# mcu-com-gpio-tim.net
KiCad netlist of a schematic drawn in Altium Designer
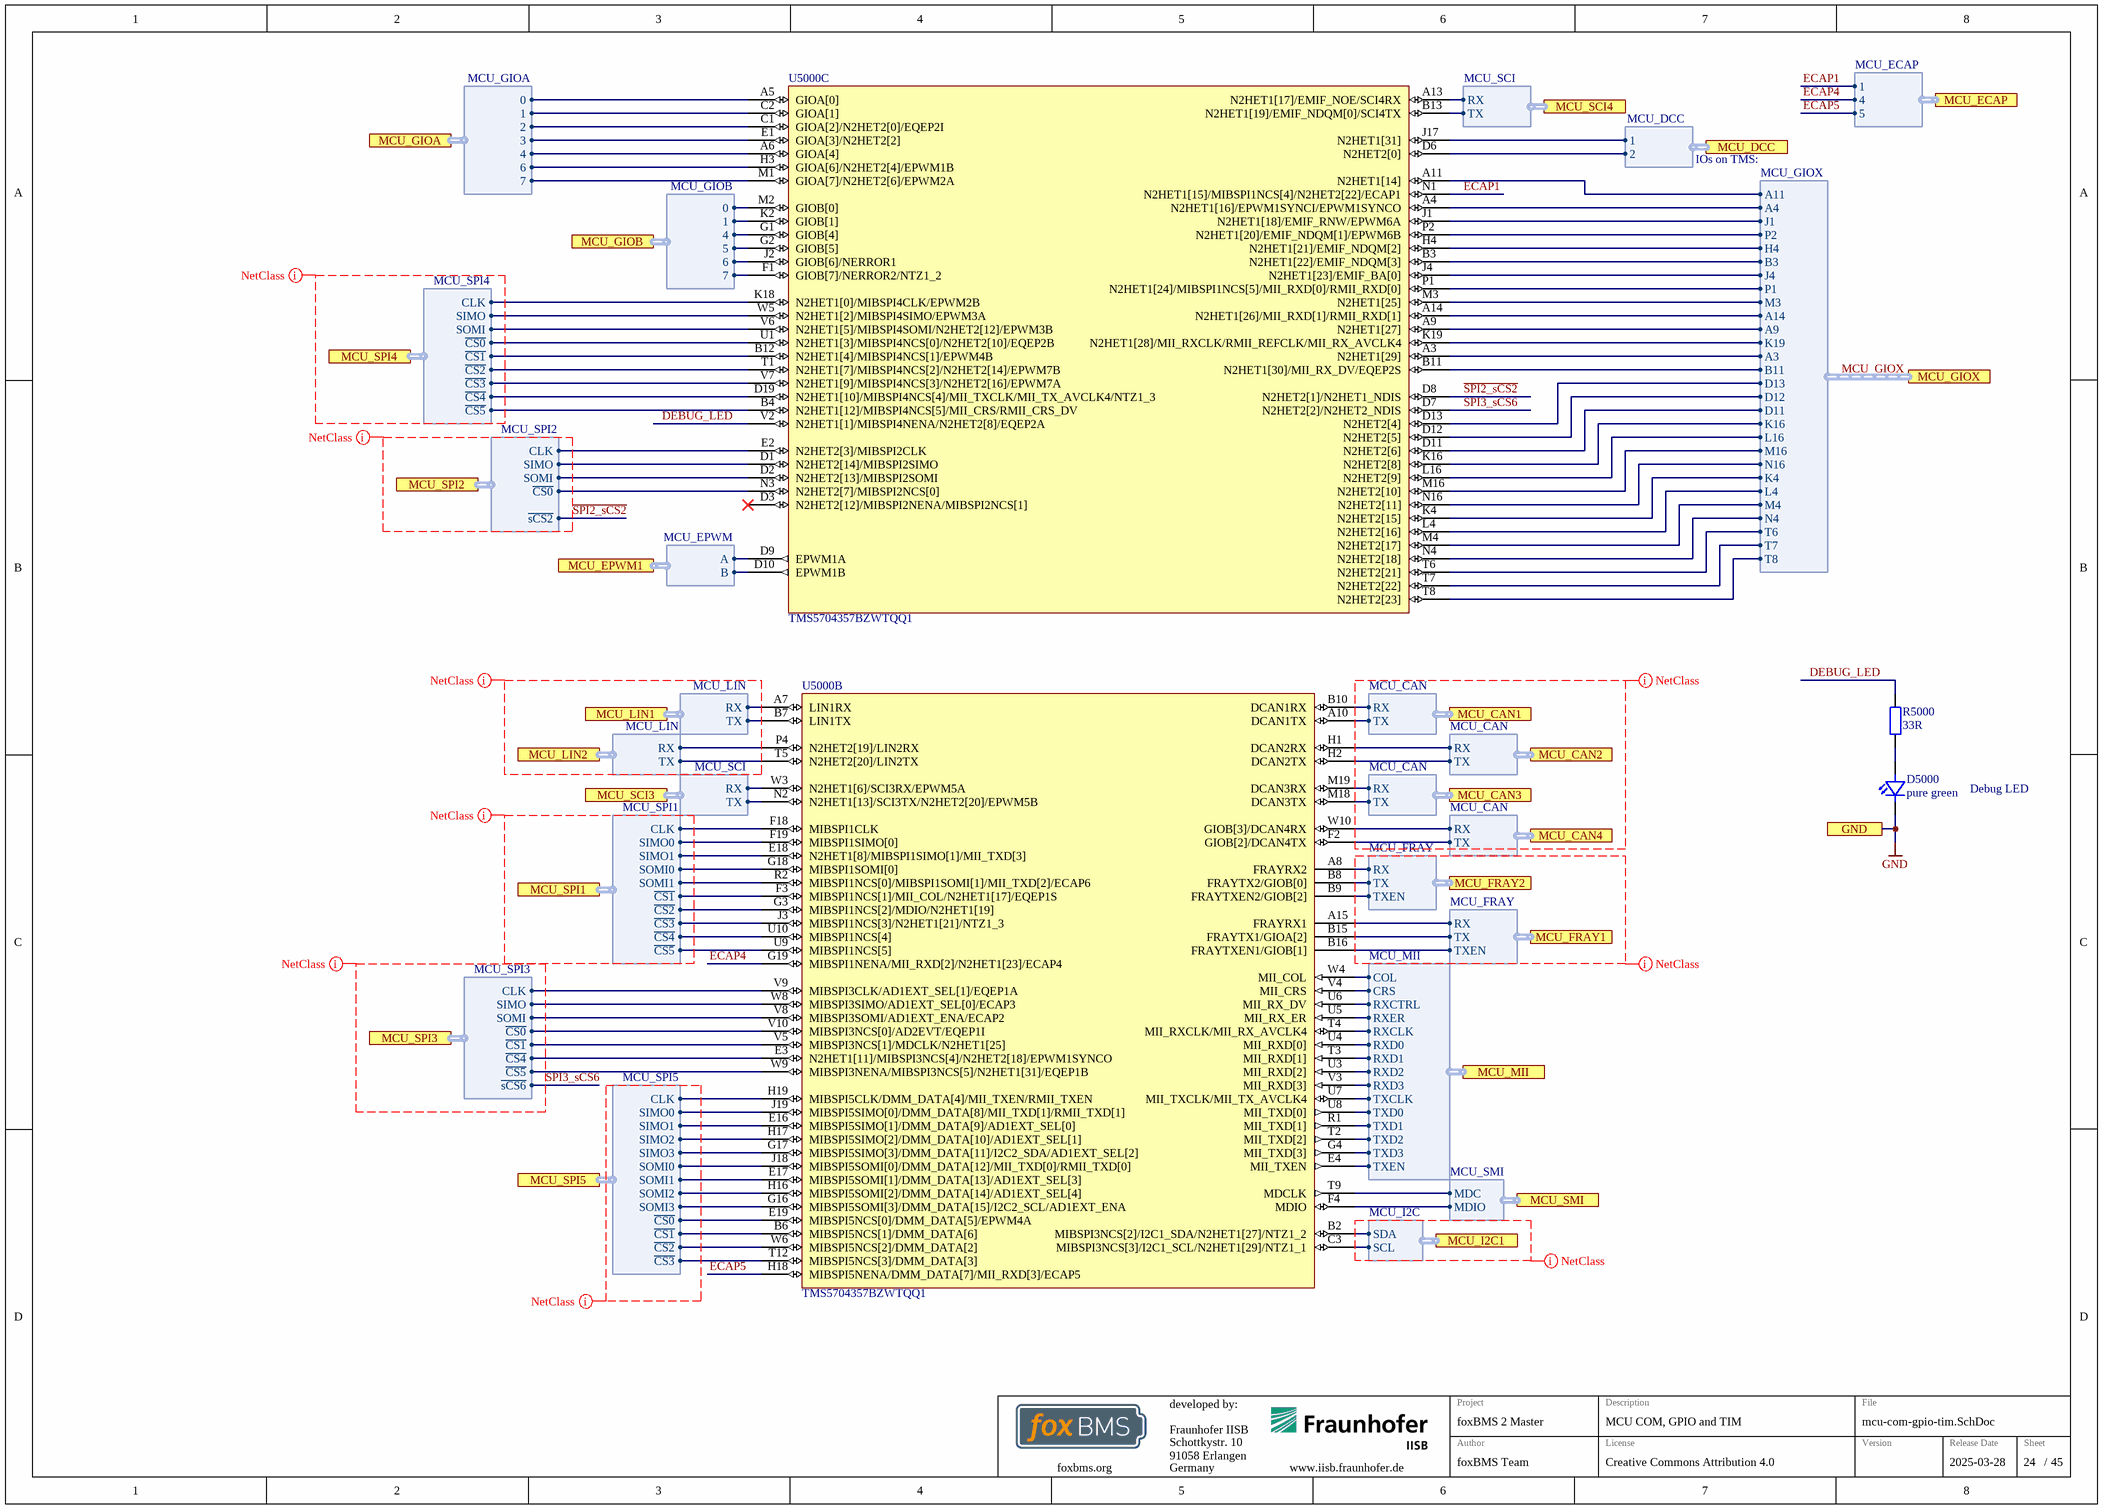
[diagram p0: mcu-com-gpio-tim.SchDoc]

(export (version "E")
  (design (tool "Eeschema 10.0.6"))
  (components
    (comp (ref "D5000")
      (value "pure green")
      (footprint "LEDC1608X07N")
      (description "TLMP1100-GS08")
      (fields (field (name "PART NUMBER") "LED_0603_pure_green_AECQ") (field (name "MANUFACTURER") "Vishay"))
      (libsource (lib "OE750") (part "D_LED"))
    )
    (comp (ref "R5000")
      (value "33R")
      (footprint "RESC1005X04N")
      (description "SMD Resistor 33R 0402")
      (fields (field (name "PART NUMBER") "gen_R_33R_0402") (field (name "TOLERANCE") "1%"))
      (libsource (lib "OE750") (part "R"))
    )
    (comp (ref "U5000")
      (value "TMS5704357BZWTQQ1")
      (footprint "BGA337C80P19X19_1600X1600X140")
      (libsource (lib "TMS570LC4357") (part "TMS5704357BZWTQQ1"))
    )
  )
  (nets
    (net (code "19") (name "/3") (class "Default")
      (node (ref "U5000") (pin "E1") (pinfunction "GIOA[3]/N2HET2[2]_E1") (pintype "bidirectional"))
    )
    (net (code "20") (name "/A") (class "Default")
      (node (ref "U5000") (pin "D9") (pinfunction "EPWM1A_D9") (pintype "output"))
    )
    (net (code "21") (name "/A3") (class "Default")
      (node (ref "U5000") (pin "A3") (pinfunction "N2HET1[29]_A3") (pintype "bidirectional"))
    )
    (net (code "22") (name "/A4") (class "Default")
      (node (ref "U5000") (pin "A4") (pinfunction "N2HET1[16]/EPWM1SYNCI/EPWM1SYNCO_A4") (pintype "bidirectional"))
    )
    (net (code "23") (name "/A9") (class "Default")
      (node (ref "U5000") (pin "A9") (pinfunction "N2HET1[27]_A9") (pintype "bidirectional"))
    )
    (net (code "24") (name "/A11") (class "Default")
      (node (ref "U5000") (pin "A11") (pinfunction "N2HET1[14]_A11") (pintype "bidirectional"))
    )
    (net (code "25") (name "/A14") (class "Default")
      (node (ref "U5000") (pin "A14") (pinfunction "N2HET1[26]/MII_RXD[1]/RMII_RXD[1]_A14") (pintype "bidirectional"))
    )
    (net (code "26") (name "/B") (class "Default")
      (node (ref "U5000") (pin "D10") (pinfunction "EPWM1B_D10") (pintype "output"))
    )
    (net (code "27") (name "/B3") (class "Default")
      (node (ref "U5000") (pin "B3") (pinfunction "N2HET1[22]/EMIF_NDQM[3]_B3") (pintype "bidirectional"))
    )
    (net (code "28") (name "/B11") (class "Default")
      (node (ref "U5000") (pin "B11") (pinfunction "N2HET1[30]/MII_RX_DV/EQEP2S_B11") (pintype "bidirectional"))
    )
    (net (code "29") (name "/COL") (class "Default")
      (node (ref "U5000") (pin "W4") (pinfunction "MII_COL_W4") (pintype "input"))
    )
    (net (code "30") (name "/CRS") (class "Default")
      (node (ref "U5000") (pin "V4") (pinfunction "MII_CRS_V4") (pintype "input"))
    )
    (net (code "31") (name "/D11") (class "Default")
      (node (ref "U5000") (pin "D11") (pinfunction "N2HET2[6]_D11") (pintype "bidirectional"))
    )
    (net (code "32") (name "/D12") (class "Default")
      (node (ref "U5000") (pin "D12") (pinfunction "N2HET2[5]_D12") (pintype "bidirectional"))
    )
    (net (code "33") (name "/D13") (class "Default")
      (node (ref "U5000") (pin "D13") (pinfunction "N2HET2[4]_D13") (pintype "bidirectional"))
    )
    (net (code "34") (name "/DEBUG_LED") (class "Default")
      (node (ref "R5000") (pin "2") (pinfunction "2_2") (pintype "passive"))
      (node (ref "U5000") (pin "V2") (pinfunction "N2HET1[1]/MIBSPI4NENA/N2HET2[8]/EQEP2A_V2") (pintype "bidirectional"))
    )
    (net (code "35") (name "/ECAP1") (class "Default")
      (node (ref "U5000") (pin "N1") (pinfunction "N2HET1[15]/MIBSPI1NCS[4]/N2HET2[22]/ECAP1_N1") (pintype "bidirectional"))
    )
    (net (code "36") (name "/ECAP4") (class "Default")
      (node (ref "U5000") (pin "G19") (pinfunction "MIBSPI1NENA/MII_RXD[2]/N2HET1[23]/ECAP4_G19") (pintype "bidirectional"))
    )
    (net (code "37") (name "/ECAP5") (class "Default")
      (node (ref "U5000") (pin "H18") (pinfunction "MIBSPI5NENA/DMM_DATA[7]/MII_RXD[3]/ECAP5_H18") (pintype "bidirectional"))
    )
    (net (code "38") (name "/H4") (class "Default")
      (node (ref "U5000") (pin "H4") (pinfunction "N2HET1[21]/EMIF_NDQM[2]_H4") (pintype "bidirectional"))
    )
    (net (code "39") (name "/J1") (class "Default")
      (node (ref "U5000") (pin "J1") (pinfunction "N2HET1[18]/EMIF_RNW/EPWM6A_J1") (pintype "bidirectional"))
    )
    (net (code "40") (name "/J4") (class "Default")
      (node (ref "U5000") (pin "J4") (pinfunction "N2HET1[23]/EMIF_BA[0]_J4") (pintype "bidirectional"))
    )
    (net (code "41") (name "/K4") (class "Default")
      (node (ref "U5000") (pin "K4") (pinfunction "N2HET2[15]_K4") (pintype "bidirectional"))
    )
    (net (code "42") (name "/K16") (class "Default")
      (node (ref "U5000") (pin "K16") (pinfunction "N2HET2[8]_K16") (pintype "bidirectional"))
    )
    (net (code "43") (name "/K19") (class "Default")
      (node (ref "U5000") (pin "K19") (pinfunction "N2HET1[28]/MII_RXCLK/RMII_REFCLK/MII_RX_AVCLK4_K19") (pintype "bidirectional"))
    )
    (net (code "44") (name "/L4") (class "Default")
      (node (ref "U5000") (pin "L4") (pinfunction "N2HET2[16]_L4") (pintype "bidirectional"))
    )
    (net (code "45") (name "/L16") (class "Default")
      (node (ref "U5000") (pin "L16") (pinfunction "N2HET2[9]_L16") (pintype "bidirectional"))
    )
    (net (code "46") (name "/M3") (class "Default")
      (node (ref "U5000") (pin "M3") (pinfunction "N2HET1[25]_M3") (pintype "bidirectional"))
    )
    (net (code "47") (name "/M4") (class "Default")
      (node (ref "U5000") (pin "M4") (pinfunction "N2HET2[17]_M4") (pintype "bidirectional"))
    )
    (net (code "48") (name "/M16") (class "Default")
      (node (ref "U5000") (pin "M16") (pinfunction "N2HET2[10]_M16") (pintype "bidirectional"))
    )
    (net (code "50") (name "/MDC") (class "Default")
      (node (ref "U5000") (pin "T9") (pinfunction "MDCLK_T9") (pintype "output"))
    )
    (net (code "51") (name "/MDIO") (class "Default")
      (node (ref "U5000") (pin "F4") (pinfunction "MDIO_F4") (pintype "bidirectional"))
    )
    (net (code "52") (name "/N4") (class "Default")
      (node (ref "U5000") (pin "N4") (pinfunction "N2HET2[18]_N4") (pintype "bidirectional"))
    )
    (net (code "53") (name "/N16") (class "Default")
      (node (ref "U5000") (pin "N16") (pinfunction "N2HET2[11]_N16") (pintype "bidirectional"))
    )
    (net (code "54") (name "/P1") (class "Default")
      (node (ref "U5000") (pin "P1") (pinfunction "N2HET1[24]/MIBSPI1NCS[5]/MII_RXD[0]/RMII_RXD[0]_P1") (pintype "bidirectional"))
    )
    (net (code "55") (name "/P2") (class "Default")
      (node (ref "U5000") (pin "P2") (pinfunction "N2HET1[20]/EMIF_NDQM[1]/EPWM6B_P2") (pintype "bidirectional"))
    )
    (net (code "56") (name "/RXCLK") (class "Default")
      (node (ref "U5000") (pin "T4") (pinfunction "MII_RXCLK/MII_RX_AVCLK4_T4") (pintype "bidirectional"))
    )
    (net (code "57") (name "/RXCTRL") (class "Default")
      (node (ref "U5000") (pin "U6") (pinfunction "MII_RX_DV_U6") (pintype "input"))
    )
    (net (code "58") (name "/RXD0") (class "Default")
      (node (ref "U5000") (pin "U4") (pinfunction "MII_RXD[0]_U4") (pintype "input"))
    )
    (net (code "59") (name "/RXD1") (class "Default")
      (node (ref "U5000") (pin "T3") (pinfunction "MII_RXD[1]_T3") (pintype "input"))
    )
    (net (code "60") (name "/RXD2") (class "Default")
      (node (ref "U5000") (pin "U3") (pinfunction "MII_RXD[2]_U3") (pintype "input"))
    )
    (net (code "61") (name "/RXD3") (class "Default")
      (node (ref "U5000") (pin "V3") (pinfunction "MII_RXD[3]_V3") (pintype "input"))
    )
    (net (code "62") (name "/RXER") (class "Default")
      (node (ref "U5000") (pin "U5") (pinfunction "MII_RX_ER_U5") (pintype "input"))
    )
    (net (code "63") (name "/SCL") (class "Default")
      (node (ref "U5000") (pin "C3") (pinfunction "MIBSPI3NCS[3]/I2C1_SCL/N2HET1[29]/NTZ1_1_C3") (pintype "bidirectional"))
    )
    (net (code "64") (name "/SDA") (class "Default")
      (node (ref "U5000") (pin "B2") (pinfunction "MIBSPI3NCS[2]/I2C1_SDA/N2HET1[27]/NTZ1_2_B2") (pintype "bidirectional"))
    )
    (net (code "65") (name "/SIMO2") (class "Default")
      (node (ref "U5000") (pin "H17") (pinfunction "MIBSPI5SIMO[2]/DMM_DATA[10]/AD1EXT_SEL[1]_H17") (pintype "bidirectional"))
    )
    (net (code "66") (name "/SIMO3") (class "Default")
      (node (ref "U5000") (pin "G17") (pinfunction "MIBSPI5SIMO[3]/DMM_DATA[11]/I2C2_SDA/AD1EXT_SEL[2]_G17") (pintype "bidirectional"))
    )
    (net (code "67") (name "/SOMI2") (class "Default")
      (node (ref "U5000") (pin "H16") (pinfunction "MIBSPI5SOMI[2]/DMM_DATA[14]/AD1EXT_SEL[4]_H16") (pintype "bidirectional"))
    )
    (net (code "68") (name "/SOMI3") (class "Default")
      (node (ref "U5000") (pin "G16") (pinfunction "MIBSPI5SOMI[3]/DMM_DATA[15]/I2C2_SCL/AD1EXT_ENA_G16") (pintype "bidirectional"))
    )
    (net (code "69") (name "/SPI2_sCS2") (class "Default")
      (node (ref "U5000") (pin "D8") (pinfunction "N2HET2[1]/N2HET1_NDIS_D8") (pintype "bidirectional"))
    )
    (net (code "70") (name "/SPI3_sCS6") (class "Default")
      (node (ref "U5000") (pin "D7") (pinfunction "N2HET2[2]/N2HET2_NDIS_D7") (pintype "bidirectional"))
    )
    (net (code "71") (name "/T6") (class "Default")
      (node (ref "U5000") (pin "T6") (pinfunction "N2HET2[21]_T6") (pintype "bidirectional"))
    )
    (net (code "72") (name "/T7") (class "Default")
      (node (ref "U5000") (pin "T7") (pinfunction "N2HET2[22]_T7") (pintype "bidirectional"))
    )
    (net (code "73") (name "/T8") (class "Default")
      (node (ref "U5000") (pin "T8") (pinfunction "N2HET2[23]_T8") (pintype "bidirectional"))
    )
    (net (code "74") (name "/TXCLK") (class "Default")
      (node (ref "U5000") (pin "U7") (pinfunction "MII_TXCLK/MII_TX_AVCLK4_U7") (pintype "bidirectional"))
    )
    (net (code "75") (name "/TXD0") (class "Default")
      (node (ref "U5000") (pin "U8") (pinfunction "MII_TXD[0]_U8") (pintype "output"))
    )
    (net (code "76") (name "/TXD1") (class "Default")
      (node (ref "U5000") (pin "R1") (pinfunction "MII_TXD[1]_R1") (pintype "output"))
    )
    (net (code "77") (name "/TXD2") (class "Default")
      (node (ref "U5000") (pin "T2") (pinfunction "MII_TXD[2]_T2") (pintype "output"))
    )
    (net (code "78") (name "/TXD3") (class "Default")
      (node (ref "U5000") (pin "G4") (pinfunction "MII_TXD[3]_G4") (pintype "output"))
    )
    (net (code "96") (name "GND") (class "Default")
      (node (ref "D5000") (pin "1") (pinfunction "C_1") (pintype "passive"))
    )
    (net (code "97") (name "Net-(D5000-A)") (class "Default")
      (node (ref "D5000") (pin "2") (pinfunction "A_2") (pintype "passive"))
      (node (ref "R5000") (pin "1") (pinfunction "1_1") (pintype "passive"))
    )
    (net (code "98") (name "unconnected-(U5000B-DCAN1RX-PadB10)") (class "Default")
      (node (ref "U5000") (pin "B10") (pinfunction "DCAN1RX_B10") (pintype "bidirectional"))
    )
    (net (code "99") (name "unconnected-(U5000B-DCAN1TX-PadA10)") (class "Default")
      (node (ref "U5000") (pin "A10") (pinfunction "DCAN1TX_A10") (pintype "bidirectional"))
    )
    (net (code "100") (name "unconnected-(U5000B-DCAN2RX-PadH1)") (class "Default")
      (node (ref "U5000") (pin "H1") (pinfunction "DCAN2RX_H1") (pintype "bidirectional"))
    )
    (net (code "101") (name "unconnected-(U5000B-DCAN2TX-PadH2)") (class "Default")
      (node (ref "U5000") (pin "H2") (pinfunction "DCAN2TX_H2") (pintype "bidirectional"))
    )
    (net (code "102") (name "unconnected-(U5000B-DCAN3RX-PadM19)") (class "Default")
      (node (ref "U5000") (pin "M19") (pinfunction "DCAN3RX_M19") (pintype "bidirectional"))
    )
    (net (code "103") (name "unconnected-(U5000B-DCAN3TX-PadM18)") (class "Default")
      (node (ref "U5000") (pin "M18") (pinfunction "DCAN3TX_M18") (pintype "bidirectional"))
    )
    (net (code "104") (name "unconnected-(U5000B-FRAYRX1-PadA15)") (class "Default")
      (node (ref "U5000") (pin "A15") (pinfunction "FRAYRX1_A15") (pintype "passive"))
    )
    (net (code "105") (name "unconnected-(U5000B-FRAYRX2-PadA8)") (class "Default")
      (node (ref "U5000") (pin "A8") (pinfunction "FRAYRX2_A8") (pintype "passive"))
    )
    (net (code "106") (name "unconnected-(U5000B-FRAYTX1{slash}GIOA[2]-PadB15)") (class "Default")
      (node (ref "U5000") (pin "B15") (pinfunction "FRAYTX1/GIOA[2]_B15") (pintype "passive"))
    )
    (net (code "107") (name "unconnected-(U5000B-FRAYTX2{slash}GIOB[0]-PadB8)") (class "Default")
      (node (ref "U5000") (pin "B8") (pinfunction "FRAYTX2/GIOB[0]_B8") (pintype "passive"))
    )
    (net (code "108") (name "unconnected-(U5000B-FRAYTXEN1{slash}GIOB[1]-PadB16)") (class "Default")
      (node (ref "U5000") (pin "B16") (pinfunction "FRAYTXEN1/GIOB[1]_B16") (pintype "passive"))
    )
    (net (code "109") (name "unconnected-(U5000B-FRAYTXEN2{slash}GIOB[2]-PadB9)") (class "Default")
      (node (ref "U5000") (pin "B9") (pinfunction "FRAYTXEN2/GIOB[2]_B9") (pintype "passive"))
    )
    (net (code "110") (name "unconnected-(U5000B-GIOB[2]{slash}DCAN4TX-PadF2)") (class "Default")
      (node (ref "U5000") (pin "F2") (pinfunction "GIOB[2]/DCAN4TX_F2") (pintype "bidirectional"))
    )
    (net (code "111") (name "unconnected-(U5000B-GIOB[3]{slash}DCAN4RX-PadW10)") (class "Default")
      (node (ref "U5000") (pin "W10") (pinfunction "GIOB[3]/DCAN4RX_W10") (pintype "bidirectional"))
    )
    (net (code "112") (name "unconnected-(U5000B-LIN1RX-PadA7)") (class "Default")
      (node (ref "U5000") (pin "A7") (pinfunction "LIN1RX_A7") (pintype "bidirectional"))
    )
    (net (code "113") (name "unconnected-(U5000B-LIN1TX-PadB7)") (class "Default")
      (node (ref "U5000") (pin "B7") (pinfunction "LIN1TX_B7") (pintype "bidirectional"))
    )
    (net (code "114") (name "unconnected-(U5000B-MIBSPI1CLK-PadF18)") (class "Default")
      (node (ref "U5000") (pin "F18") (pinfunction "MIBSPI1CLK_F18") (pintype "bidirectional"))
    )
    (net (code "115") (name "unconnected-(U5000B-MIBSPI1NCS[0]{slash}MIBSPI1SOMI[1]{slash}MII_TXD[2]{slash}ECAP6-PadR2)") (class "Default")
      (node (ref "U5000") (pin "R2") (pinfunction "MIBSPI1NCS[0]/MIBSPI1SOMI[1]/MII_TXD[2]/ECAP6_R2") (pintype "bidirectional"))
    )
    (net (code "116") (name "unconnected-(U5000B-MIBSPI1NCS[1]{slash}MII_COL{slash}N2HET1[17]{slash}EQEP1S-PadF3)") (class "Default")
      (node (ref "U5000") (pin "F3") (pinfunction "MIBSPI1NCS[1]/MII_COL/N2HET1[17]/EQEP1S_F3") (pintype "bidirectional"))
    )
    (net (code "117") (name "unconnected-(U5000B-MIBSPI1NCS[2]{slash}MDIO{slash}N2HET1[19]-PadG3)") (class "Default")
      (node (ref "U5000") (pin "G3") (pinfunction "MIBSPI1NCS[2]/MDIO/N2HET1[19]_G3") (pintype "bidirectional"))
    )
    (net (code "118") (name "unconnected-(U5000B-MIBSPI1NCS[3]{slash}N2HET1[21]{slash}NTZ1_3-PadJ3)") (class "Default")
      (node (ref "U5000") (pin "J3") (pinfunction "MIBSPI1NCS[3]/N2HET1[21]/NTZ1_3_J3") (pintype "bidirectional"))
    )
    (net (code "119") (name "unconnected-(U5000B-MIBSPI1NCS[4]-PadU10)") (class "Default")
      (node (ref "U5000") (pin "U10") (pinfunction "MIBSPI1NCS[4]_U10") (pintype "bidirectional"))
    )
    (net (code "120") (name "unconnected-(U5000B-MIBSPI1NCS[5]-PadU9)") (class "Default")
      (node (ref "U5000") (pin "U9") (pinfunction "MIBSPI1NCS[5]_U9") (pintype "bidirectional"))
    )
    (net (code "121") (name "unconnected-(U5000B-MIBSPI1SIMO[0]-PadF19)") (class "Default")
      (node (ref "U5000") (pin "F19") (pinfunction "MIBSPI1SIMO[0]_F19") (pintype "bidirectional"))
    )
    (net (code "122") (name "unconnected-(U5000B-MIBSPI1SOMI[0]-PadG18)") (class "Default")
      (node (ref "U5000") (pin "G18") (pinfunction "MIBSPI1SOMI[0]_G18") (pintype "bidirectional"))
    )
    (net (code "123") (name "unconnected-(U5000B-MIBSPI3CLK{slash}AD1EXT_SEL[1]{slash}EQEP1A-PadV9)") (class "Default")
      (node (ref "U5000") (pin "V9") (pinfunction "MIBSPI3CLK/AD1EXT_SEL[1]/EQEP1A_V9") (pintype "bidirectional"))
    )
    (net (code "124") (name "unconnected-(U5000B-MIBSPI3NCS[0]{slash}AD2EVT{slash}EQEP1I-PadV10)") (class "Default")
      (node (ref "U5000") (pin "V10") (pinfunction "MIBSPI3NCS[0]/AD2EVT/EQEP1I_V10") (pintype "bidirectional"))
    )
    (net (code "125") (name "unconnected-(U5000B-MIBSPI3NCS[1]{slash}MDCLK{slash}N2HET1[25]-PadV5)") (class "Default")
      (node (ref "U5000") (pin "V5") (pinfunction "MIBSPI3NCS[1]/MDCLK/N2HET1[25]_V5") (pintype "bidirectional"))
    )
    (net (code "126") (name "unconnected-(U5000B-MIBSPI3NENA{slash}MIBSPI3NCS[5]{slash}N2HET1[31]{slash}EQEP1B-PadW9)") (class "Default")
      (node (ref "U5000") (pin "W9") (pinfunction "MIBSPI3NENA/MIBSPI3NCS[5]/N2HET1[31]/EQEP1B_W9") (pintype "bidirectional"))
    )
    (net (code "127") (name "unconnected-(U5000B-MIBSPI3SIMO{slash}AD1EXT_SEL[0]{slash}ECAP3-PadW8)") (class "Default")
      (node (ref "U5000") (pin "W8") (pinfunction "MIBSPI3SIMO/AD1EXT_SEL[0]/ECAP3_W8") (pintype "bidirectional"))
    )
    (net (code "128") (name "unconnected-(U5000B-MIBSPI3SOMI{slash}AD1EXT_ENA{slash}ECAP2-PadV8)") (class "Default")
      (node (ref "U5000") (pin "V8") (pinfunction "MIBSPI3SOMI/AD1EXT_ENA/ECAP2_V8") (pintype "bidirectional"))
    )
    (net (code "129") (name "unconnected-(U5000B-MIBSPI5CLK{slash}DMM_DATA[4]{slash}MII_TXEN{slash}RMII_TXEN-PadH19)") (class "Default")
      (node (ref "U5000") (pin "H19") (pinfunction "MIBSPI5CLK/DMM_DATA[4]/MII_TXEN/RMII_TXEN_H19") (pintype "bidirectional"))
    )
    (net (code "130") (name "unconnected-(U5000B-MIBSPI5NCS[0]{slash}DMM_DATA[5]{slash}EPWM4A-PadE19)") (class "Default")
      (node (ref "U5000") (pin "E19") (pinfunction "MIBSPI5NCS[0]/DMM_DATA[5]/EPWM4A_E19") (pintype "bidirectional"))
    )
    (net (code "131") (name "unconnected-(U5000B-MIBSPI5NCS[1]{slash}DMM_DATA[6]-PadB6)") (class "Default")
      (node (ref "U5000") (pin "B6") (pinfunction "MIBSPI5NCS[1]/DMM_DATA[6]_B6") (pintype "bidirectional"))
    )
    (net (code "132") (name "unconnected-(U5000B-MIBSPI5NCS[2]{slash}DMM_DATA[2]-PadW6)") (class "Default")
      (node (ref "U5000") (pin "W6") (pinfunction "MIBSPI5NCS[2]/DMM_DATA[2]_W6") (pintype "bidirectional"))
    )
    (net (code "133") (name "unconnected-(U5000B-MIBSPI5NCS[3]{slash}DMM_DATA[3]-PadT12)") (class "Default")
      (node (ref "U5000") (pin "T12") (pinfunction "MIBSPI5NCS[3]/DMM_DATA[3]_T12") (pintype "bidirectional"))
    )
    (net (code "134") (name "unconnected-(U5000B-MIBSPI5SIMO[0]{slash}DMM_DATA[8]{slash}MII_TXD[1]{slash}RMII_TXD[1]-PadJ19)") (class "Default")
      (node (ref "U5000") (pin "J19") (pinfunction "MIBSPI5SIMO[0]/DMM_DATA[8]/MII_TXD[1]/RMII_TXD[1]_J19") (pintype "bidirectional"))
    )
    (net (code "135") (name "unconnected-(U5000B-MIBSPI5SIMO[1]{slash}DMM_DATA[9]{slash}AD1EXT_SEL[0]-PadE16)") (class "Default")
      (node (ref "U5000") (pin "E16") (pinfunction "MIBSPI5SIMO[1]/DMM_DATA[9]/AD1EXT_SEL[0]_E16") (pintype "bidirectional"))
    )
    (net (code "136") (name "unconnected-(U5000B-MIBSPI5SOMI[0]{slash}DMM_DATA[12]{slash}MII_TXD[0]{slash}RMII_TXD[0]-PadJ18)") (class "Default")
      (node (ref "U5000") (pin "J18") (pinfunction "MIBSPI5SOMI[0]/DMM_DATA[12]/MII_TXD[0]/RMII_TXD[0]_J18") (pintype "bidirectional"))
    )
    (net (code "137") (name "unconnected-(U5000B-MIBSPI5SOMI[1]{slash}DMM_DATA[13]{slash}AD1EXT_SEL[3]-PadE17)") (class "Default")
      (node (ref "U5000") (pin "E17") (pinfunction "MIBSPI5SOMI[1]/DMM_DATA[13]/AD1EXT_SEL[3]_E17") (pintype "bidirectional"))
    )
    (net (code "138") (name "unconnected-(U5000B-MII_TXEN-PadE4)") (class "Default")
      (node (ref "U5000") (pin "E4") (pinfunction "MII_TXEN_E4") (pintype "output"))
    )
    (net (code "139") (name "unconnected-(U5000B-N2HET1[6]{slash}SCI3RX{slash}EPWM5A-PadW3)") (class "Default")
      (node (ref "U5000") (pin "W3") (pinfunction "N2HET1[6]/SCI3RX/EPWM5A_W3") (pintype "bidirectional"))
    )
    (net (code "140") (name "unconnected-(U5000B-N2HET1[8]{slash}MIBSPI1SIMO[1]{slash}MII_TXD[3]-PadE18)") (class "Default")
      (node (ref "U5000") (pin "E18") (pinfunction "N2HET1[8]/MIBSPI1SIMO[1]/MII_TXD[3]_E18") (pintype "bidirectional"))
    )
    (net (code "141") (name "unconnected-(U5000B-N2HET1[11]{slash}MIBSPI3NCS[4]{slash}N2HET2[18]{slash}EPWM1SYNCO-PadE3)") (class "Default")
      (node (ref "U5000") (pin "E3") (pinfunction "N2HET1[11]/MIBSPI3NCS[4]/N2HET2[18]/EPWM1SYNCO_E3") (pintype "bidirectional"))
    )
    (net (code "142") (name "unconnected-(U5000B-N2HET1[13]{slash}SCI3TX{slash}N2HET2[20]{slash}EPWM5B-PadN2)") (class "Default")
      (node (ref "U5000") (pin "N2") (pinfunction "N2HET1[13]/SCI3TX/N2HET2[20]/EPWM5B_N2") (pintype "bidirectional"))
    )
    (net (code "143") (name "unconnected-(U5000B-N2HET2[19]{slash}LIN2RX-PadP4)") (class "Default")
      (node (ref "U5000") (pin "P4") (pinfunction "N2HET2[19]/LIN2RX_P4") (pintype "bidirectional"))
    )
    (net (code "144") (name "unconnected-(U5000B-N2HET2[20]{slash}LIN2TX-PadT5)") (class "Default")
      (node (ref "U5000") (pin "T5") (pinfunction "N2HET2[20]/LIN2TX_T5") (pintype "bidirectional"))
    )
    (net (code "145") (name "unconnected-(U5000C-GIOA[0]-PadA5)") (class "Default")
      (node (ref "U5000") (pin "A5") (pinfunction "GIOA[0]_A5") (pintype "bidirectional"))
    )
    (net (code "146") (name "unconnected-(U5000C-GIOA[1]-PadC2)") (class "Default")
      (node (ref "U5000") (pin "C2") (pinfunction "GIOA[1]_C2") (pintype "bidirectional"))
    )
    (net (code "147") (name "unconnected-(U5000C-GIOA[2]{slash}N2HET2[0]{slash}EQEP2I-PadC1)") (class "Default")
      (node (ref "U5000") (pin "C1") (pinfunction "GIOA[2]/N2HET2[0]/EQEP2I_C1") (pintype "bidirectional"))
    )
    (net (code "148") (name "unconnected-(U5000C-GIOA[4]-PadA6)") (class "Default")
      (node (ref "U5000") (pin "A6") (pinfunction "GIOA[4]_A6") (pintype "bidirectional"))
    )
    (net (code "149") (name "unconnected-(U5000C-GIOA[6]{slash}N2HET2[4]{slash}EPWM1B-PadH3)") (class "Default")
      (node (ref "U5000") (pin "H3") (pinfunction "GIOA[6]/N2HET2[4]/EPWM1B_H3") (pintype "bidirectional"))
    )
    (net (code "150") (name "unconnected-(U5000C-GIOA[7]{slash}N2HET2[6]{slash}EPWM2A-PadM1)") (class "Default")
      (node (ref "U5000") (pin "M1") (pinfunction "GIOA[7]/N2HET2[6]/EPWM2A_M1") (pintype "bidirectional"))
    )
    (net (code "151") (name "unconnected-(U5000C-GIOB[0]-PadM2)") (class "Default")
      (node (ref "U5000") (pin "M2") (pinfunction "GIOB[0]_M2") (pintype "bidirectional"))
    )
    (net (code "152") (name "unconnected-(U5000C-GIOB[1]-PadK2)") (class "Default")
      (node (ref "U5000") (pin "K2") (pinfunction "GIOB[1]_K2") (pintype "bidirectional"))
    )
    (net (code "153") (name "unconnected-(U5000C-GIOB[4]-PadG1)") (class "Default")
      (node (ref "U5000") (pin "G1") (pinfunction "GIOB[4]_G1") (pintype "bidirectional"))
    )
    (net (code "154") (name "unconnected-(U5000C-GIOB[5]-PadG2)") (class "Default")
      (node (ref "U5000") (pin "G2") (pinfunction "GIOB[5]_G2") (pintype "bidirectional"))
    )
    (net (code "155") (name "unconnected-(U5000C-GIOB[6]{slash}NERROR1-PadJ2)") (class "Default")
      (node (ref "U5000") (pin "J2") (pinfunction "GIOB[6]/NERROR1_J2") (pintype "bidirectional"))
    )
    (net (code "156") (name "unconnected-(U5000C-GIOB[7]{slash}NERROR2{slash}NTZ1_2-PadF1)") (class "Default")
      (node (ref "U5000") (pin "F1") (pinfunction "GIOB[7]/NERROR2/NTZ1_2_F1") (pintype "bidirectional"))
    )
    (net (code "157") (name "unconnected-(U5000C-N2HET1[0]{slash}MIBSPI4CLK{slash}EPWM2B-PadK18)") (class "Default")
      (node (ref "U5000") (pin "K18") (pinfunction "N2HET1[0]/MIBSPI4CLK/EPWM2B_K18") (pintype "bidirectional"))
    )
    (net (code "158") (name "unconnected-(U5000C-N2HET1[2]{slash}MIBSPI4SIMO{slash}EPWM3A-PadW5)") (class "Default")
      (node (ref "U5000") (pin "W5") (pinfunction "N2HET1[2]/MIBSPI4SIMO/EPWM3A_W5") (pintype "bidirectional"))
    )
    (net (code "159") (name "unconnected-(U5000C-N2HET1[3]{slash}MIBSPI4NCS[0]{slash}N2HET2[10]{slash}EQEP2B-PadU1)") (class "Default")
      (node (ref "U5000") (pin "U1") (pinfunction "N2HET1[3]/MIBSPI4NCS[0]/N2HET2[10]/EQEP2B_U1") (pintype "bidirectional"))
    )
    (net (code "160") (name "unconnected-(U5000C-N2HET1[4]{slash}MIBSPI4NCS[1]{slash}EPWM4B-PadB12)") (class "Default")
      (node (ref "U5000") (pin "B12") (pinfunction "N2HET1[4]/MIBSPI4NCS[1]/EPWM4B_B12") (pintype "bidirectional"))
    )
    (net (code "161") (name "unconnected-(U5000C-N2HET1[5]{slash}MIBSPI4SOMI{slash}N2HET2[12]{slash}EPWM3B-PadV6)") (class "Default")
      (node (ref "U5000") (pin "V6") (pinfunction "N2HET1[5]/MIBSPI4SOMI/N2HET2[12]/EPWM3B_V6") (pintype "bidirectional"))
    )
    (net (code "162") (name "unconnected-(U5000C-N2HET1[7]{slash}MIBSPI4NCS[2]{slash}N2HET2[14]{slash}EPWM7B-PadT1)") (class "Default")
      (node (ref "U5000") (pin "T1") (pinfunction "N2HET1[7]/MIBSPI4NCS[2]/N2HET2[14]/EPWM7B_T1") (pintype "bidirectional"))
    )
    (net (code "163") (name "unconnected-(U5000C-N2HET1[9]{slash}MIBSPI4NCS[3]{slash}N2HET2[16]{slash}EPWM7A-PadV7)") (class "Default")
      (node (ref "U5000") (pin "V7") (pinfunction "N2HET1[9]/MIBSPI4NCS[3]/N2HET2[16]/EPWM7A_V7") (pintype "bidirectional"))
    )
    (net (code "164") (name "unconnected-(U5000C-N2HET1[10]{slash}MIBSPI4NCS[4]{slash}MII_TXCLK{slash}MII_TX_AVCLK4{slash}NTZ1_3-PadD19)") (class "Default")
      (node (ref "U5000") (pin "D19") (pinfunction "N2HET1[10]/MIBSPI4NCS[4]/MII_TXCLK/MII_TX_AVCLK4/NTZ1_3_D19") (pintype "bidirectional"))
    )
    (net (code "165") (name "unconnected-(U5000C-N2HET1[12]{slash}MIBSPI4NCS[5]{slash}MII_CRS{slash}RMII_CRS_DV-PadB4)") (class "Default")
      (node (ref "U5000") (pin "B4") (pinfunction "N2HET1[12]/MIBSPI4NCS[5]/MII_CRS/RMII_CRS_DV_B4") (pintype "bidirectional"))
    )
    (net (code "166") (name "unconnected-(U5000C-N2HET1[17]{slash}EMIF_NOE{slash}SCI4RX-PadA13)") (class "Default")
      (node (ref "U5000") (pin "A13") (pinfunction "N2HET1[17]/EMIF_NOE/SCI4RX_A13") (pintype "bidirectional"))
    )
    (net (code "167") (name "unconnected-(U5000C-N2HET1[19]{slash}EMIF_NDQM[0]{slash}SCI4TX-PadB13)") (class "Default")
      (node (ref "U5000") (pin "B13") (pinfunction "N2HET1[19]/EMIF_NDQM[0]/SCI4TX_B13") (pintype "bidirectional"))
    )
    (net (code "168") (name "unconnected-(U5000C-N2HET1[31]-PadJ17)") (class "Default")
      (node (ref "U5000") (pin "J17") (pinfunction "N2HET1[31]_J17") (pintype "bidirectional"))
    )
    (net (code "169") (name "unconnected-(U5000C-N2HET2[0]-PadD6)") (class "Default")
      (node (ref "U5000") (pin "D6") (pinfunction "N2HET2[0]_D6") (pintype "bidirectional"))
    )
    (net (code "170") (name "unconnected-(U5000C-N2HET2[3]{slash}MIBSPI2CLK-PadE2)") (class "Default")
      (node (ref "U5000") (pin "E2") (pinfunction "N2HET2[3]/MIBSPI2CLK_E2") (pintype "bidirectional"))
    )
    (net (code "171") (name "unconnected-(U5000C-N2HET2[7]{slash}MIBSPI2NCS[0]-PadN3)") (class "Default")
      (node (ref "U5000") (pin "N3") (pinfunction "N2HET2[7]/MIBSPI2NCS[0]_N3") (pintype "bidirectional"))
    )
    (net (code "172") (name "unconnected-(U5000C-N2HET2[12]{slash}MIBSPI2NENA{slash}MIBSPI2NCS[1]-PadD3)") (class "Default")
      (node (ref "U5000") (pin "D3") (pinfunction "N2HET2[12]/MIBSPI2NENA/MIBSPI2NCS[1]_D3") (pintype "bidirectional+no_connect"))
    )
    (net (code "173") (name "unconnected-(U5000C-N2HET2[13]{slash}MIBSPI2SOMI-PadD2)") (class "Default")
      (node (ref "U5000") (pin "D2") (pinfunction "N2HET2[13]/MIBSPI2SOMI_D2") (pintype "bidirectional"))
    )
    (net (code "174") (name "unconnected-(U5000C-N2HET2[14]{slash}MIBSPI2SIMO-PadD1)") (class "Default")
      (node (ref "U5000") (pin "D1") (pinfunction "N2HET2[14]/MIBSPI2SIMO_D1") (pintype "bidirectional"))
    )
  )
)
